# Ela.net
KiCad netlist of a schematic drawn in EAGLE
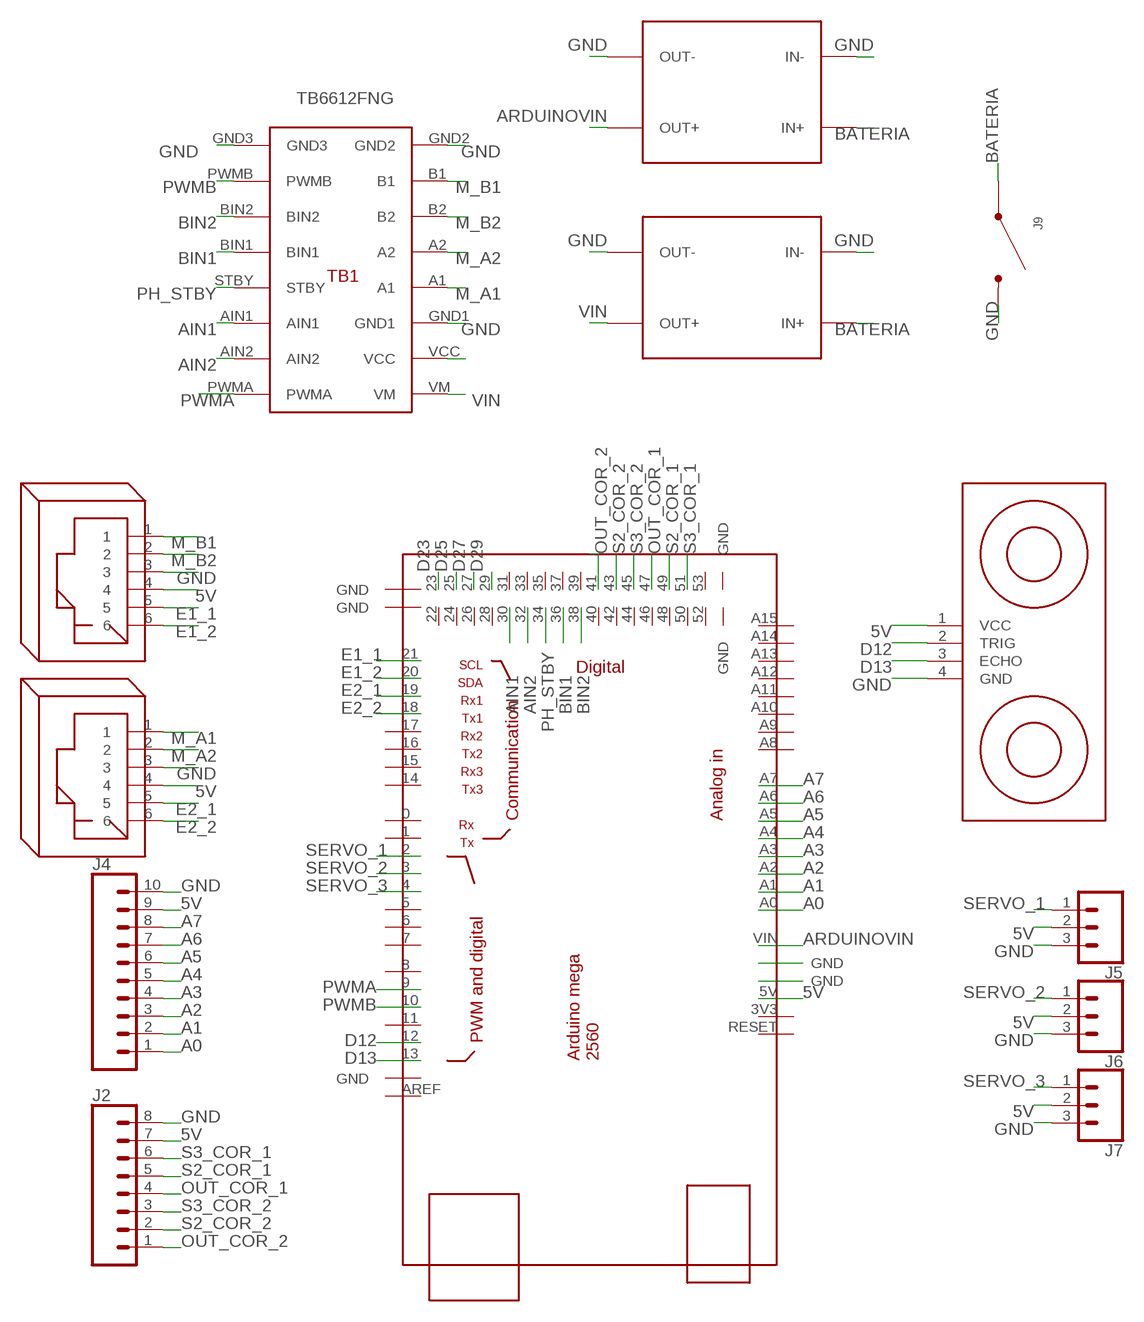
[diagram p0: schematic, sheet 1]

(export (version "E")
  (design (tool "Eeschema 10.0.6"))
  (components
    (comp (ref "J1")
      (value "RJ12")
      (footprint "eagle-import:RJ12")
      (libsource (lib "eagle-import") (part "RJ12"))
    )
    (comp (ref "J2")
      (value "CONN_08LONGPADS")
      (footprint "eagle-import:1X08_LONGPADS")
      (libsource (lib "eagle-import") (part "CONN_08LONGPADS"))
    )
    (comp (ref "J3")
      (value "RJ12")
      (footprint "eagle-import:RJ12")
      (libsource (lib "eagle-import") (part "RJ12"))
    )
    (comp (ref "J4")
      (value "CONN_10\"")
      (footprint "eagle-import:1X10")
      (libsource (lib "eagle-import") (part "CONN_10{dblquote}"))
    )
    (comp (ref "J5")
      (value "CONN_03LONGPADS")
      (footprint "eagle-import:1X03_LONGPADS")
      (libsource (lib "eagle-import") (part "CONN_03LONGPADS"))
    )
    (comp (ref "J6")
      (value "CONN_03LONGPADS")
      (footprint "eagle-import:1X03_LONGPADS")
      (libsource (lib "eagle-import") (part "CONN_03LONGPADS"))
    )
    (comp (ref "J7")
      (value "CONN_03LONGPADS")
      (footprint "eagle-import:1X03_LONGPADS")
      (libsource (lib "eagle-import") (part "CONN_03LONGPADS"))
    )
    (comp (ref "J9")
      (value "XT60TOP")
      (footprint "eagle-import:XT60_TOP")
      (libsource (lib "eagle-import") (part "XT60TOP"))
    )
    (comp (ref "TB1")
      (value "TB6612FNG")
      (footprint "eagle-import:TB6612FNG")
      (libsource (lib "eagle-import") (part "TB6612FNG"))
    )
    (comp (ref "U$1")
      (value "ULTRASONIC-HC-SR04#V")
      (footprint "eagle-import:ULTRASONIC-HC-SR04#V")
      (libsource (lib "eagle-import") (part "ULTRASONIC-HC-SR04#V"))
    )
    (comp (ref "U$2")
      (value "DC-DC-STEP-DOWN-LM2596")
      (footprint "eagle-import:DC-DC-STEP-DOWN-LM2596")
      (libsource (lib "eagle-import") (part "DC-DC-STEP-DOWN-LM2596"))
    )
    (comp (ref "U$3")
      (value "MEGA_DEVICE")
      (footprint "eagle-import:MEGAOUTLINE")
      (libsource (lib "eagle-import") (part "MEGA_DEVICE"))
    )
    (comp (ref "U$4")
      (value "DC-DC-STEP-DOWN-LM2596")
      (footprint "eagle-import:DC-DC-STEP-DOWN-LM2596")
      (libsource (lib "eagle-import") (part "DC-DC-STEP-DOWN-LM2596"))
    )
  )
  (nets
    (net (code "1") (name "/5V") (class "Default")
      (node (ref "J1") (pin "4") (pinfunction "4_4") (pintype "bidirectional"))
      (node (ref "J2") (pin "7") (pinfunction "7_7") (pintype "passive"))
      (node (ref "J3") (pin "4") (pinfunction "4_4") (pintype "bidirectional"))
      (node (ref "J4") (pin "9") (pinfunction "9_9") (pintype "passive"))
      (node (ref "J5") (pin "2") (pinfunction "2_2") (pintype "passive"))
      (node (ref "J6") (pin "2") (pinfunction "2_2") (pintype "passive"))
      (node (ref "J7") (pin "2") (pinfunction "2_2") (pintype "passive"))
      (node (ref "TB1") (pin "VCC") (pinfunction "VCC_VCC") (pintype "bidirectional"))
      (node (ref "U$1") (pin "1") (pinfunction "VCC_1") (pintype "power_in"))
      (node (ref "U$3") (pin "5V") (pinfunction "5V_5V") (pintype "bidirectional"))
    )
    (net (code "2") (name "/A0") (class "Default")
      (node (ref "J4") (pin "1") (pinfunction "1_1") (pintype "passive"))
      (node (ref "U$3") (pin "A0") (pinfunction "A0_A0") (pintype "bidirectional"))
    )
    (net (code "3") (name "/A1") (class "Default")
      (node (ref "J4") (pin "2") (pinfunction "2_2") (pintype "passive"))
      (node (ref "U$3") (pin "A1") (pinfunction "A1_A1") (pintype "bidirectional"))
    )
    (net (code "4") (name "/A2") (class "Default")
      (node (ref "J4") (pin "3") (pinfunction "3_3") (pintype "passive"))
      (node (ref "U$3") (pin "A2") (pinfunction "A2_A2") (pintype "bidirectional"))
    )
    (net (code "5") (name "/A3") (class "Default")
      (node (ref "J4") (pin "4") (pinfunction "4_4") (pintype "passive"))
      (node (ref "U$3") (pin "A3") (pinfunction "A3_A3") (pintype "bidirectional"))
    )
    (net (code "6") (name "/A4") (class "Default")
      (node (ref "J4") (pin "5") (pinfunction "5_5") (pintype "passive"))
      (node (ref "U$3") (pin "A4") (pinfunction "A4_A4") (pintype "bidirectional"))
    )
    (net (code "7") (name "/A5") (class "Default")
      (node (ref "J4") (pin "6") (pinfunction "6_6") (pintype "passive"))
      (node (ref "U$3") (pin "A5") (pinfunction "A5_A5") (pintype "bidirectional"))
    )
    (net (code "8") (name "/A6") (class "Default")
      (node (ref "J4") (pin "7") (pinfunction "7_7") (pintype "passive"))
      (node (ref "U$3") (pin "A6") (pinfunction "A6_A6") (pintype "bidirectional"))
    )
    (net (code "9") (name "/A7") (class "Default")
      (node (ref "J4") (pin "8") (pinfunction "8_8") (pintype "passive"))
      (node (ref "U$3") (pin "A7") (pinfunction "A7_A7") (pintype "bidirectional"))
    )
    (net (code "10") (name "/AIN1") (class "Default")
      (node (ref "TB1") (pin "AIN1") (pinfunction "AIN1_AIN1") (pintype "bidirectional"))
      (node (ref "U$3") (pin "30") (pinfunction "30_30") (pintype "bidirectional"))
    )
    (net (code "11") (name "/AIN2") (class "Default")
      (node (ref "TB1") (pin "AIN2") (pinfunction "AIN2_AIN2") (pintype "bidirectional"))
      (node (ref "U$3") (pin "32") (pinfunction "32_32") (pintype "bidirectional"))
    )
    (net (code "12") (name "/ARDUINOVIN") (class "Default")
      (node (ref "U$3") (pin "VIN") (pinfunction "VIN_VIN") (pintype "bidirectional"))
      (node (ref "U$4") (pin "OUT+") (pinfunction "OUT+_OUT+") (pintype "bidirectional"))
    )
    (net (code "13") (name "/BATERIA") (class "Default")
      (node (ref "J9") (pin "P$+") (pinfunction "+_P$+") (pintype "power_in"))
      (node (ref "U$2") (pin "IN+") (pinfunction "IN+_IN+") (pintype "bidirectional"))
      (node (ref "U$4") (pin "IN+") (pinfunction "IN+_IN+") (pintype "bidirectional"))
    )
    (net (code "14") (name "/BIN1") (class "Default")
      (node (ref "TB1") (pin "BIN1") (pinfunction "BIN1_BIN1") (pintype "bidirectional"))
      (node (ref "U$3") (pin "36") (pinfunction "36_36") (pintype "bidirectional"))
    )
    (net (code "15") (name "/BIN2") (class "Default")
      (node (ref "TB1") (pin "BIN2") (pinfunction "BIN2_BIN2") (pintype "bidirectional"))
      (node (ref "U$3") (pin "38") (pinfunction "38_38") (pintype "bidirectional"))
    )
    (net (code "16") (name "/D12") (class "Default")
      (node (ref "U$1") (pin "2") (pinfunction "TRIG_2") (pintype "input"))
      (node (ref "U$3") (pin "12") (pinfunction "12_12") (pintype "bidirectional"))
    )
    (net (code "17") (name "/D13") (class "Default")
      (node (ref "U$1") (pin "3") (pinfunction "ECHO_3") (pintype "output"))
      (node (ref "U$3") (pin "13") (pinfunction "13_13") (pintype "bidirectional"))
    )
    (net (code "18") (name "/D23") (class "Default")
      (node (ref "U$3") (pin "23") (pinfunction "23_23") (pintype "bidirectional"))
    )
    (net (code "19") (name "/D25") (class "Default")
      (node (ref "U$3") (pin "25") (pinfunction "25_25") (pintype "bidirectional"))
    )
    (net (code "20") (name "/D27") (class "Default")
      (node (ref "U$3") (pin "27") (pinfunction "27_27") (pintype "bidirectional"))
    )
    (net (code "21") (name "/D29") (class "Default")
      (node (ref "U$3") (pin "29") (pinfunction "29_29") (pintype "bidirectional"))
    )
    (net (code "22") (name "/E1_1") (class "Default")
      (node (ref "J1") (pin "5") (pinfunction "5_5") (pintype "bidirectional"))
      (node (ref "U$3") (pin "21") (pinfunction "21_21") (pintype "bidirectional"))
    )
    (net (code "23") (name "/E1_2") (class "Default")
      (node (ref "J1") (pin "6") (pinfunction "6_6") (pintype "bidirectional"))
      (node (ref "U$3") (pin "20") (pinfunction "20_20") (pintype "bidirectional"))
    )
    (net (code "24") (name "/E2_1") (class "Default")
      (node (ref "J3") (pin "5") (pinfunction "5_5") (pintype "bidirectional"))
      (node (ref "U$3") (pin "19") (pinfunction "19_19") (pintype "bidirectional"))
    )
    (net (code "25") (name "/E2_2") (class "Default")
      (node (ref "J3") (pin "6") (pinfunction "6_6") (pintype "bidirectional"))
      (node (ref "U$3") (pin "18") (pinfunction "18_18") (pintype "bidirectional"))
    )
    (net (code "26") (name "/GND") (class "Default")
      (node (ref "J1") (pin "3") (pinfunction "3_3") (pintype "bidirectional"))
      (node (ref "J2") (pin "8") (pinfunction "8_8") (pintype "passive"))
      (node (ref "J3") (pin "3") (pinfunction "3_3") (pintype "bidirectional"))
      (node (ref "J4") (pin "10") (pinfunction "10_10") (pintype "passive"))
      (node (ref "J5") (pin "3") (pinfunction "3_3") (pintype "passive"))
      (node (ref "J6") (pin "3") (pinfunction "3_3") (pintype "passive"))
      (node (ref "J7") (pin "3") (pinfunction "3_3") (pintype "passive"))
      (node (ref "J9") (pin "P$-") (pinfunction "-_P$-") (pintype "power_in"))
      (node (ref "TB1") (pin "GND1") (pinfunction "GND1_GND1") (pintype "bidirectional"))
      (node (ref "TB1") (pin "GND2") (pinfunction "GND2_GND2") (pintype "bidirectional"))
      (node (ref "TB1") (pin "GND3") (pinfunction "GND3_GND3") (pintype "bidirectional"))
      (node (ref "U$1") (pin "4") (pinfunction "GND_4") (pintype "power_in"))
      (node (ref "U$2") (pin "IN-") (pinfunction "IN-_IN-") (pintype "bidirectional"))
      (node (ref "U$2") (pin "OUT-") (pinfunction "OUT-_OUT-") (pintype "bidirectional"))
      (node (ref "U$4") (pin "IN-") (pinfunction "IN-_IN-") (pintype "bidirectional"))
      (node (ref "U$4") (pin "OUT-") (pinfunction "OUT-_OUT-") (pintype "bidirectional"))
    )
    (net (code "27") (name "/M_A1") (class "Default")
      (node (ref "J3") (pin "1") (pinfunction "1_1") (pintype "bidirectional"))
      (node (ref "TB1") (pin "A1") (pinfunction "A1_A1") (pintype "bidirectional"))
    )
    (net (code "28") (name "/M_A2") (class "Default")
      (node (ref "J3") (pin "2") (pinfunction "2_2") (pintype "bidirectional"))
      (node (ref "TB1") (pin "A2") (pinfunction "A2_A2") (pintype "bidirectional"))
    )
    (net (code "29") (name "/M_B1") (class "Default")
      (node (ref "J1") (pin "1") (pinfunction "1_1") (pintype "bidirectional"))
      (node (ref "TB1") (pin "B1") (pinfunction "B1_B1") (pintype "bidirectional"))
    )
    (net (code "30") (name "/M_B2") (class "Default")
      (node (ref "J1") (pin "2") (pinfunction "2_2") (pintype "bidirectional"))
      (node (ref "TB1") (pin "B2") (pinfunction "B2_B2") (pintype "bidirectional"))
    )
    (net (code "31") (name "/OUT_COR_1") (class "Default")
      (node (ref "J2") (pin "4") (pinfunction "4_4") (pintype "passive"))
      (node (ref "U$3") (pin "47") (pinfunction "47_47") (pintype "bidirectional"))
    )
    (net (code "32") (name "/OUT_COR_2") (class "Default")
      (node (ref "J2") (pin "1") (pinfunction "1_1") (pintype "passive"))
      (node (ref "U$3") (pin "41") (pinfunction "41_41") (pintype "bidirectional"))
    )
    (net (code "33") (name "/PH_STBY") (class "Default")
      (node (ref "TB1") (pin "STBY") (pinfunction "STBY_STBY") (pintype "bidirectional"))
      (node (ref "U$3") (pin "34") (pinfunction "34_34") (pintype "bidirectional"))
    )
    (net (code "34") (name "/PWMA") (class "Default")
      (node (ref "TB1") (pin "PWMA") (pinfunction "PWMA_PWMA") (pintype "bidirectional"))
      (node (ref "U$3") (pin "9") (pinfunction "9_9") (pintype "bidirectional"))
    )
    (net (code "35") (name "/PWMB") (class "Default")
      (node (ref "TB1") (pin "PWMB") (pinfunction "PWMB_PWMB") (pintype "bidirectional"))
      (node (ref "U$3") (pin "10") (pinfunction "10_10") (pintype "bidirectional"))
    )
    (net (code "36") (name "/S2_COR_1") (class "Default")
      (node (ref "J2") (pin "5") (pinfunction "5_5") (pintype "passive"))
      (node (ref "U$3") (pin "49") (pinfunction "49_49") (pintype "bidirectional"))
    )
    (net (code "37") (name "/S2_COR_2") (class "Default")
      (node (ref "J2") (pin "2") (pinfunction "2_2") (pintype "passive"))
      (node (ref "U$3") (pin "43") (pinfunction "43_43") (pintype "bidirectional"))
    )
    (net (code "38") (name "/S3_COR_1") (class "Default")
      (node (ref "J2") (pin "6") (pinfunction "6_6") (pintype "passive"))
      (node (ref "U$3") (pin "51") (pinfunction "51_51") (pintype "bidirectional"))
    )
    (net (code "39") (name "/S3_COR_2") (class "Default")
      (node (ref "J2") (pin "3") (pinfunction "3_3") (pintype "passive"))
      (node (ref "U$3") (pin "45") (pinfunction "45_45") (pintype "bidirectional"))
    )
    (net (code "40") (name "/SERVO_1") (class "Default")
      (node (ref "J5") (pin "1") (pinfunction "1_1") (pintype "passive"))
      (node (ref "U$3") (pin "2") (pinfunction "2_2") (pintype "bidirectional"))
    )
    (net (code "41") (name "/SERVO_2") (class "Default")
      (node (ref "J6") (pin "1") (pinfunction "1_1") (pintype "passive"))
      (node (ref "U$3") (pin "3") (pinfunction "3_3") (pintype "bidirectional"))
    )
    (net (code "42") (name "/SERVO_3") (class "Default")
      (node (ref "J7") (pin "1") (pinfunction "1_1") (pintype "passive"))
      (node (ref "U$3") (pin "4") (pinfunction "4_4") (pintype "bidirectional"))
    )
    (net (code "43") (name "/VIN") (class "Default")
      (node (ref "TB1") (pin "VM") (pinfunction "VM_VM") (pintype "bidirectional"))
      (node (ref "U$2") (pin "OUT+") (pinfunction "OUT+_OUT+") (pintype "bidirectional"))
    )
    (net (code "44") (name "unconnected-(U$3-GND-PadGND@1)") (class "Default")
      (node (ref "U$3") (pin "GND@1") (pinfunction "GND_GND@1") (pintype "bidirectional"))
    )
    (net (code "45") (name "unconnected-(U$3-GND-PadGND@2)") (class "Default")
      (node (ref "U$3") (pin "GND@2") (pinfunction "GND_GND@2") (pintype "bidirectional"))
    )
    (net (code "46") (name "unconnected-(U$3-GND-PadGND@3)") (class "Default")
      (node (ref "U$3") (pin "GND@3") (pinfunction "GND_GND@3") (pintype "bidirectional"))
    )
    (net (code "47") (name "unconnected-(U$3-GND-PadGND@4)") (class "Default")
      (node (ref "U$3") (pin "GND@4") (pinfunction "GND_GND@4") (pintype "bidirectional"))
    )
    (net (code "48") (name "unconnected-(U$3-GND-PadGND@5)") (class "Default")
      (node (ref "U$3") (pin "GND@5") (pinfunction "GND_GND@5") (pintype "bidirectional"))
    )
    (net (code "49") (name "unconnected-(U$3-GND-PadGND@6)") (class "Default")
      (node (ref "U$3") (pin "GND@6") (pinfunction "GND_GND@6") (pintype "bidirectional"))
    )
    (net (code "50") (name "unconnected-(U$3-GND-PadGND@7)") (class "Default")
      (node (ref "U$3") (pin "GND@7") (pinfunction "GND_GND@7") (pintype "bidirectional"))
    )
    (net (code "51") (name "unconnected-(U$3-Pad0)") (class "Default")
      (node (ref "U$3") (pin "0") (pinfunction "0_0") (pintype "bidirectional"))
    )
    (net (code "52") (name "unconnected-(U$3-Pad1)") (class "Default")
      (node (ref "U$3") (pin "1") (pinfunction "1_1") (pintype "bidirectional"))
    )
    (net (code "53") (name "unconnected-(U$3-Pad3V3)") (class "Default")
      (node (ref "U$3") (pin "3V3") (pinfunction "3V3_3V3") (pintype "bidirectional"))
    )
    (net (code "54") (name "unconnected-(U$3-Pad5)") (class "Default")
      (node (ref "U$3") (pin "5") (pinfunction "5_5") (pintype "bidirectional"))
    )
    (net (code "55") (name "unconnected-(U$3-Pad6)") (class "Default")
      (node (ref "U$3") (pin "6") (pinfunction "6_6") (pintype "bidirectional"))
    )
    (net (code "56") (name "unconnected-(U$3-Pad7)") (class "Default")
      (node (ref "U$3") (pin "7") (pinfunction "7_7") (pintype "bidirectional"))
    )
    (net (code "57") (name "unconnected-(U$3-Pad8)") (class "Default")
      (node (ref "U$3") (pin "8") (pinfunction "8_8") (pintype "bidirectional"))
    )
    (net (code "58") (name "unconnected-(U$3-Pad11)") (class "Default")
      (node (ref "U$3") (pin "11") (pinfunction "11_11") (pintype "bidirectional"))
    )
    (net (code "59") (name "unconnected-(U$3-Pad14)") (class "Default")
      (node (ref "U$3") (pin "14") (pinfunction "14_14") (pintype "bidirectional"))
    )
    (net (code "60") (name "unconnected-(U$3-Pad15)") (class "Default")
      (node (ref "U$3") (pin "15") (pinfunction "15_15") (pintype "bidirectional"))
    )
    (net (code "61") (name "unconnected-(U$3-Pad16)") (class "Default")
      (node (ref "U$3") (pin "16") (pinfunction "16_16") (pintype "bidirectional"))
    )
    (net (code "62") (name "unconnected-(U$3-Pad17)") (class "Default")
      (node (ref "U$3") (pin "17") (pinfunction "17_17") (pintype "bidirectional"))
    )
    (net (code "63") (name "unconnected-(U$3-Pad22)") (class "Default")
      (node (ref "U$3") (pin "22") (pinfunction "22_22") (pintype "bidirectional"))
    )
    (net (code "64") (name "unconnected-(U$3-Pad24)") (class "Default")
      (node (ref "U$3") (pin "24") (pinfunction "24_24") (pintype "bidirectional"))
    )
    (net (code "65") (name "unconnected-(U$3-Pad26)") (class "Default")
      (node (ref "U$3") (pin "26") (pinfunction "26_26") (pintype "bidirectional"))
    )
    (net (code "66") (name "unconnected-(U$3-Pad28)") (class "Default")
      (node (ref "U$3") (pin "28") (pinfunction "28_28") (pintype "bidirectional"))
    )
    (net (code "67") (name "unconnected-(U$3-Pad31)") (class "Default")
      (node (ref "U$3") (pin "31") (pinfunction "31_31") (pintype "bidirectional"))
    )
    (net (code "68") (name "unconnected-(U$3-Pad33)") (class "Default")
      (node (ref "U$3") (pin "33") (pinfunction "33_33") (pintype "bidirectional"))
    )
    (net (code "69") (name "unconnected-(U$3-Pad35)") (class "Default")
      (node (ref "U$3") (pin "35") (pinfunction "35_35") (pintype "bidirectional"))
    )
    (net (code "70") (name "unconnected-(U$3-Pad37)") (class "Default")
      (node (ref "U$3") (pin "37") (pinfunction "37_37") (pintype "bidirectional"))
    )
    (net (code "71") (name "unconnected-(U$3-Pad39)") (class "Default")
      (node (ref "U$3") (pin "39") (pinfunction "39_39") (pintype "bidirectional"))
    )
    (net (code "72") (name "unconnected-(U$3-Pad40)") (class "Default")
      (node (ref "U$3") (pin "40") (pinfunction "40_40") (pintype "bidirectional"))
    )
    (net (code "73") (name "unconnected-(U$3-Pad42)") (class "Default")
      (node (ref "U$3") (pin "42") (pinfunction "42_42") (pintype "bidirectional"))
    )
    (net (code "74") (name "unconnected-(U$3-Pad44)") (class "Default")
      (node (ref "U$3") (pin "44") (pinfunction "44_44") (pintype "bidirectional"))
    )
    (net (code "75") (name "unconnected-(U$3-Pad46)") (class "Default")
      (node (ref "U$3") (pin "46") (pinfunction "46_46") (pintype "bidirectional"))
    )
    (net (code "76") (name "unconnected-(U$3-Pad48)") (class "Default")
      (node (ref "U$3") (pin "48") (pinfunction "48_48") (pintype "bidirectional"))
    )
    (net (code "77") (name "unconnected-(U$3-Pad50)") (class "Default")
      (node (ref "U$3") (pin "50") (pinfunction "50_50") (pintype "bidirectional"))
    )
    (net (code "78") (name "unconnected-(U$3-Pad52)") (class "Default")
      (node (ref "U$3") (pin "52") (pinfunction "52_52") (pintype "bidirectional"))
    )
    (net (code "79") (name "unconnected-(U$3-Pad53)") (class "Default")
      (node (ref "U$3") (pin "53") (pinfunction "53_53") (pintype "bidirectional"))
    )
    (net (code "80") (name "unconnected-(U$3-PadA8)") (class "Default")
      (node (ref "U$3") (pin "A8") (pinfunction "A8_A8") (pintype "bidirectional"))
    )
    (net (code "81") (name "unconnected-(U$3-PadA9)") (class "Default")
      (node (ref "U$3") (pin "A9") (pinfunction "A9_A9") (pintype "bidirectional"))
    )
    (net (code "82") (name "unconnected-(U$3-PadA10)") (class "Default")
      (node (ref "U$3") (pin "A10") (pinfunction "A10_A10") (pintype "bidirectional"))
    )
    (net (code "83") (name "unconnected-(U$3-PadA11)") (class "Default")
      (node (ref "U$3") (pin "A11") (pinfunction "A11_A11") (pintype "bidirectional"))
    )
    (net (code "84") (name "unconnected-(U$3-PadA12)") (class "Default")
      (node (ref "U$3") (pin "A12") (pinfunction "A12_A12") (pintype "bidirectional"))
    )
    (net (code "85") (name "unconnected-(U$3-PadA13)") (class "Default")
      (node (ref "U$3") (pin "A13") (pinfunction "A13_A13") (pintype "bidirectional"))
    )
    (net (code "86") (name "unconnected-(U$3-PadA14)") (class "Default")
      (node (ref "U$3") (pin "A14") (pinfunction "A14_A14") (pintype "bidirectional"))
    )
    (net (code "87") (name "unconnected-(U$3-PadA15)") (class "Default")
      (node (ref "U$3") (pin "A15") (pinfunction "A15_A15") (pintype "bidirectional"))
    )
    (net (code "88") (name "unconnected-(U$3-PadAREF)") (class "Default")
      (node (ref "U$3") (pin "AREF") (pinfunction "AREF_AREF") (pintype "bidirectional"))
    )
    (net (code "89") (name "unconnected-(U$3-PadRESET)") (class "Default")
      (node (ref "U$3") (pin "RESET") (pinfunction "RESET_RESET") (pintype "bidirectional"))
    )
  )
)
